# 04_Incense_MCU.net
KiCad netlist of a schematic drawn in Altium Designer
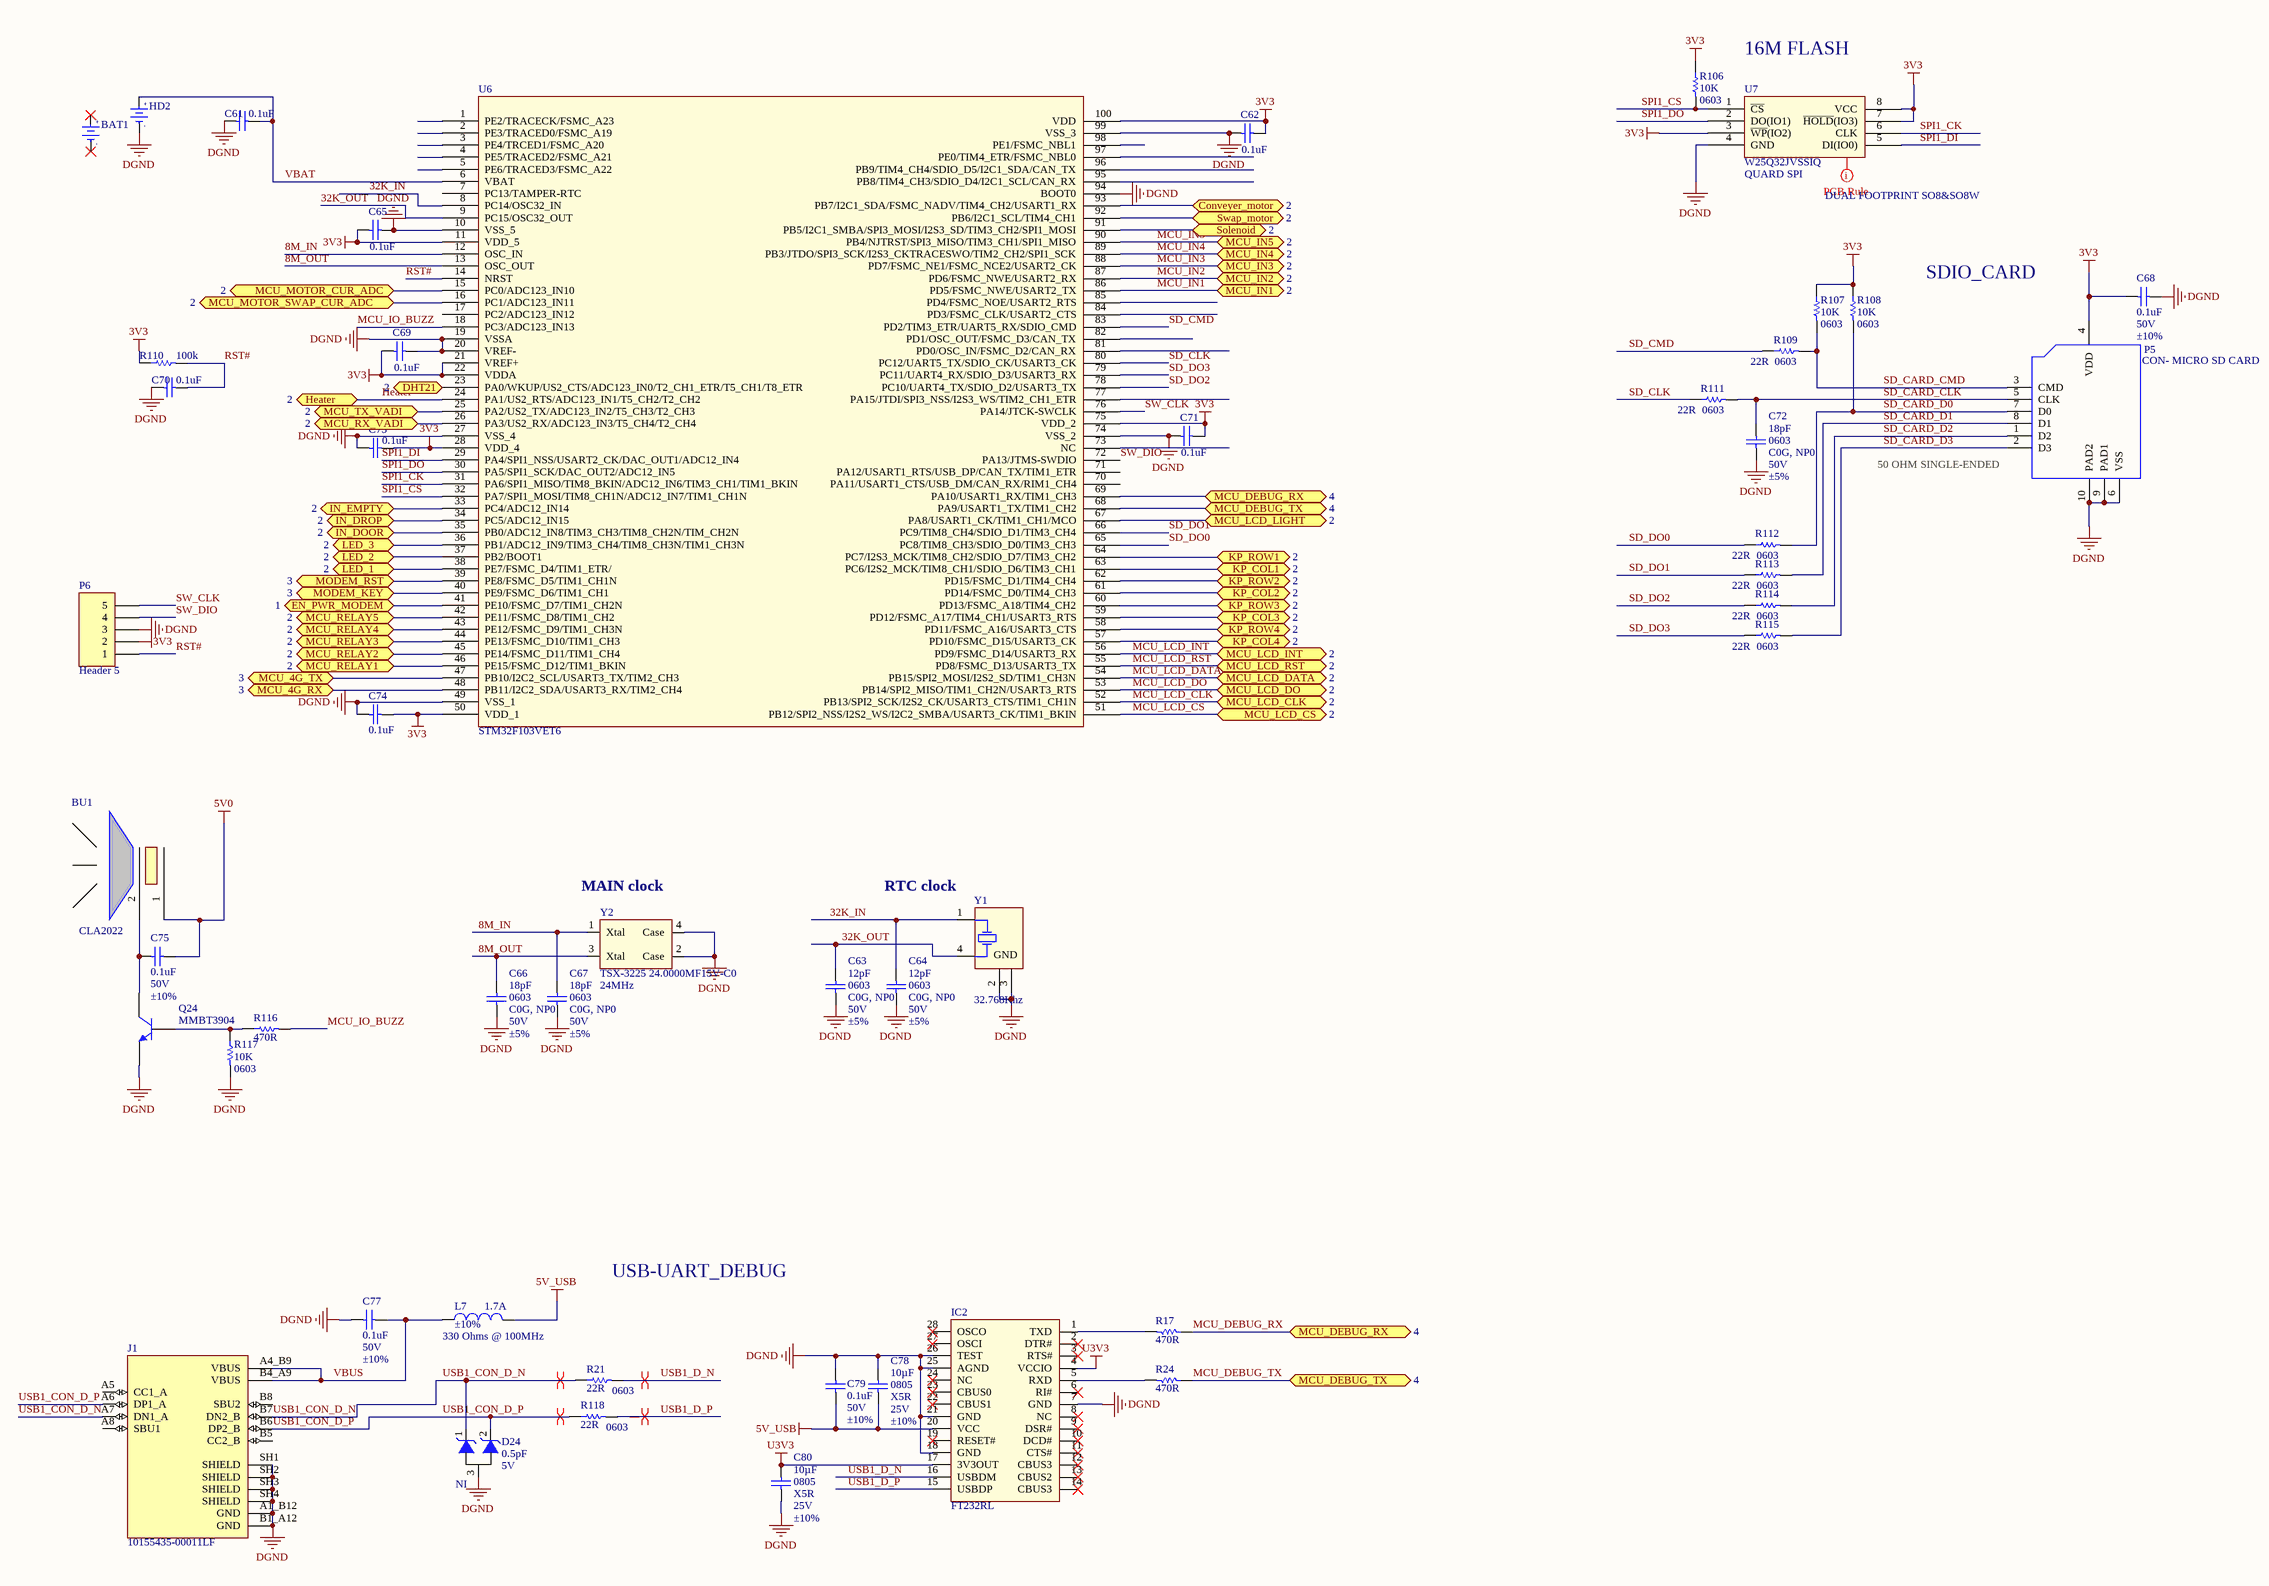
[diagram p0: 04_Incense_MCU.SchDoc]

(export (version "E")
  (design (tool "Eeschema 10.0.6"))
  (components
    (comp (ref "BAT1")
      (value "CR1220")
      (footprint "De Pin Cr1220")
      (description "CR1220 BATTERY")
      (fields (field (name "MANUFACTURER1_PART#") "PIN CR1220 Lithium"))
      (libsource (lib "Schlib1") (part "CR1220 SMD"))
    )
    (comp (ref "BU1")
      (value "CLA2022")
      (footprint "BUZZ_5V_D12X7.5MM")
      (description "BUZZ 5V 12095 12x9.5mm")
      (fields (field (name "MANUFACTURER2_PART#") "5V 9.5x12MM"))
      (libsource (lib "VSM_SES-MAIN_REV04B") (part "PKM13EPYH4000"))
    )
    (comp (ref "C61")
      (value "0.1uF,0805,16v")
      (footprint "CAP 0603")
      (description "CAP CER 0.1UF 50V X7R 0603")
      (fields
        (field (name "=VALUE") "0.1uF")
        (field (name "MANUFACTURER1_PART#") "CL10B104KB8NNNC")
        (field (name "PUBLISHER") "Altium Limited")
      )
      (libsource (lib "Miscellaneous Devices") (part "Cap"))
    )
    (comp (ref "C62")
      (value "Cap")
      (footprint "CAP 0603")
      (description "CAP CER 0.1UF 50V X7R 0603")
      (fields
        (field (name "=VALUE") "0.1uF")
        (field (name "MANUFACTURER1_PART#") "CL10B104KB8NNNC")
        (field (name "PUBLISHER") "Altium Limited")
      )
      (libsource (lib "Miscellaneous Devices") (part "Cap"))
    )
    (comp (ref "C63")
      (value "12pF")
      (footprint "0603")
      (description "CAP-CER,SMD;12PF,5%,50V,C0G/NPO 0603")
      (fields
        (field (name "MATERIAL") "C0G, NP0")
        (field (name "VOLTAGE") "50V")
        (field (name "TOLERANCE") "±5%")
        (field (name "MANUFACTURER1_PART#") "CC0603JRNPO9BN120")
      )
      (libsource (lib "Slider") (part "Cap"))
    )
    (comp (ref "C64")
      (value "12pF")
      (footprint "0603")
      (description "CAP-CER,SMD;12PF,5%,50V,C0G/NPO 0603")
      (fields
        (field (name "MATERIAL") "C0G, NP0")
        (field (name "VOLTAGE") "50V")
        (field (name "TOLERANCE") "±5%")
        (field (name "MANUFACTURER1_PART#") "CC0603JRNPO9BN120")
      )
      (libsource (lib "Slider") (part "Cap"))
    )
    (comp (ref "C65")
      (value "Cap")
      (footprint "cap 0603")
      (description "CAP CER 0.1UF 50V X7R 0603")
      (fields
        (field (name "=VALUE") "0.1uF")
        (field (name "MANUFACTURER1_PART#") "CL10B104KB8NNNC")
        (field (name "PUBLISHER") "Altium Limited")
      )
      (libsource (lib "Miscellaneous Devices") (part "Cap"))
    )
    (comp (ref "C66")
      (value "18pF")
      (footprint "0603")
      (description "CAP CER 18PF 50V C0G/NP0 0603")
      (fields
        (field (name "MATERIAL") "C0G, NP0")
        (field (name "VOLTAGE") "50V")
        (field (name "TOLERANCE") "±5%")
        (field (name "MANUFACTURER1_PART#") "CL10C180JB81PNC")
        (field (name "MANUFACTURER2_PART#") "CC0603JRNPO9BN180")
      )
      (libsource (lib "Slider") (part "Cap"))
    )
    (comp (ref "C67")
      (value "18pF")
      (footprint "0603")
      (description "CAP CER 18PF 50V C0G/NP0 0603")
      (fields
        (field (name "MATERIAL") "C0G, NP0")
        (field (name "VOLTAGE") "50V")
        (field (name "TOLERANCE") "±5%")
        (field (name "MANUFACTURER1_PART#") "CL10C180JB81PNC")
        (field (name "MANUFACTURER2_PART#") "CC0603JRNPO9BN180")
      )
      (libsource (lib "Slider") (part "Cap"))
    )
    (comp (ref "C68")
      (value "0.1uF")
      (footprint "CAP 0603")
      (description "CAP-CER,SMD;0.1UF,10%,50V,X7R,0603")
      (fields
        (field (name "VOLTAGE") "50V")
        (field (name "TOLERANCE") "±10%")
        (field (name "MANUFACTURER1_PART#") "CL10B104KB8NNNC")
        (field (name "MANUFACTURER2_PART#") "M0603X104K050TAX")
      )
      (libsource (lib "Slider") (part "Cap"))
    )
    (comp (ref "C69")
      (value "Cap")
      (footprint "CAP 0603")
      (description "CAP CER 0.1UF 50V X7R 0603")
      (fields
        (field (name "=VALUE") "0.1uF")
        (field (name "MANUFACTURER1_PART#") "CL10B104KB8NNNC")
        (field (name "PUBLISHER") "Altium Limited")
      )
      (libsource (lib "Miscellaneous Devices") (part "Cap"))
    )
    (comp (ref "C70")
      (value "Cap")
      (footprint "CAP 0603")
      (description "CAP CER 0.1UF 50V X7R 0603")
      (fields
        (field (name "=VALUE") "0.1uF")
        (field (name "MANUFACTURER1_PART#") "CL10B104KB8NNNC")
        (field (name "PUBLISHER") "Altium Limited")
      )
      (libsource (lib "Miscellaneous Devices") (part "Cap"))
    )
    (comp (ref "C71")
      (value "0.1uF")
      (footprint "CAP 0603")
      (description "CAP-CER,SMD;0.1UF,10%,50V,X7R,0603")
      (fields
        (field (name "MANUFACTURER1_PART#") "CL10B104KB8NNNC")
        (field (name "Comment") "Cap")
        (field (name "PUBLISHER") "Altium Limited")
      )
      (libsource (lib "Miscellaneous Devices") (part "Cap"))
    )
    (comp (ref "C72")
      (value "18pF")
      (footprint "0603")
      (description "CAP CER 18PF 50V C0G/NP0 0603")
      (fields
        (field (name "MATERIAL") "C0G, NP0")
        (field (name "VOLTAGE") "50V")
        (field (name "TOLERANCE") "±5%")
        (field (name "MANUFACTURER1_PART#") "CL10C180JB81PNC")
        (field (name "MANUFACTURER2_PART#") "CC0603JRNPO9BN180")
      )
      (libsource (lib "Slider") (part "Cap"))
    )
    (comp (ref "C73")
      (value "0.1uF")
      (footprint "CAP 0603")
      (description "CAP-CER,SMD;0.1UF,10%,50V,X7R,0603")
      (fields
        (field (name "MANUFACTURER1_PART#") "CL10B104KB8NNNC")
        (field (name "Comment") "Cap")
        (field (name "PUBLISHER") "Altium Limited")
      )
      (libsource (lib "Miscellaneous Devices") (part "Cap"))
    )
    (comp (ref "C74")
      (value "0.1uF")
      (footprint "CAP 0603")
      (description "CAP-CER,SMD;0.1UF,10%,50V,X7R,0603")
      (fields
        (field (name "MANUFACTURER1_PART#") "CL10B104KB8NNNC")
        (field (name "Comment") "Cap")
        (field (name "PUBLISHER") "Altium Limited")
      )
      (libsource (lib "Miscellaneous Devices") (part "Cap"))
    )
    (comp (ref "C75")
      (value "0.1uF")
      (footprint "CAP 0603")
      (description "CAP-CER,SMD;0.1UF,10%,50V,X7R,0603")
      (fields
        (field (name "VOLTAGE") "50V")
        (field (name "TOLERANCE") "±10%")
        (field (name "MANUFACTURER1_PART#") "CL10B104KB8NNNC")
        (field (name "MANUFACTURER2_PART#") "M0603X104K050TAX")
      )
      (libsource (lib "Slider") (part "Cap"))
    )
    (comp (ref "C77")
      (value "0.1uF")
      (footprint "CAP 0603")
      (description "CAP-CER,SMD;0.1UF,10%,50V,X7R,0603")
      (fields
        (field (name "VOLTAGE") "50V")
        (field (name "TOLERANCE") "±10%")
        (field (name "MANUFACTURER1_PART#") "CL10B104KB8NNNC")
        (field (name "MANUFACTURER2_PART#") "M0603X104K050TAX")
      )
      (libsource (lib "Slider") (part "Cap"))
    )
    (comp (ref "C78")
      (value "10µF")
      (footprint "CAP 0805")
      (description "CAP-CER,SMD;10UF,10%,25V,X5R,0805")
      (fields
        (field (name "MANUFACTURER1_PART#") "TMK212BBJ106KG-T")
        (field (name "MANUFACTURER2_PART#") "CL21A106KAYNNNG")
        (field (name "PACKAGE") "0805")
        (field (name "VOLTAGE") "25V")
        (field (name "TOLERANCE") "±10%")
        (field (name "MATERIAL") "X5R")
      )
      (libsource (lib "Full") (part "Cap-NP-100"))
    )
    (comp (ref "C79")
      (value "0.1uF")
      (footprint "CAP 0603")
      (description "CAP-CER,SMD;0.1UF,10%,50V,X7R,0603")
      (fields
        (field (name "VOLTAGE") "50V")
        (field (name "TOLERANCE") "±10%")
        (field (name "MANUFACTURER1_PART#") "CL10B104KB8NNNC")
        (field (name "MANUFACTURER2_PART#") "M0603X104K050TAX")
      )
      (libsource (lib "Slider") (part "Cap"))
    )
    (comp (ref "C80")
      (value "10µF")
      (footprint "CAP 0805")
      (description "CAP-CER,SMD;10UF,10%,25V,X5R,0805")
      (fields
        (field (name "MANUFACTURER1_PART#") "TMK212BBJ106KG-T")
        (field (name "MANUFACTURER2_PART#") "CL21A106KAYNNNG")
        (field (name "PACKAGE") "0805")
        (field (name "VOLTAGE") "25V")
        (field (name "TOLERANCE") "±10%")
        (field (name "MATERIAL") "X5R")
      )
      (libsource (lib "Full") (part "Cap-NP-100"))
    )
    (comp (ref "D24")
      (value "ESDR0502BT1G")
      (footprint "SOT-416")
      (description "5V, ESD PROTECTION DEVICES, SOT-23")
      (fields
        (field (name "MANUFACTURER2_PART#") "DF3D6.8MS,LF")
        (field (name "POWER") "320W")
        (field (name "CAPACITANCE") "0.5pF")
        (field (name "VOLTAGE") "5V")
        (field (name "NI_MARK") "NI")
      )
      (libsource (lib "My Library") (part "TVS_DUAL_SIGNAL_5V_SOT23"))
    )
    (comp (ref "HD2")
      (value "CR1220-2ZX")
      (footprint "BATTERY HOLDER CR1220 SMD")
      (description "CR1220 SMD HOLDER")
      (fields (field (name "MANUFACTURER2_PART#") "BH-122A-5"))
      (libsource (lib "Schlib1") (part "CR1220 SMD"))
    )
    (comp (ref "IC2")
      (value "FT232RL")
      (footprint "FT232")
      (description "IC USB FS SERIAL UART 28-SSOP")
      (fields
        (field (name "MANUFACTURER1_PART#") "FT232RL-REEL")
        (field (name "MANUFACTURER2_PART#") "PL2303HX")
      )
      (libsource (lib "PART") (part "PL2303HX"))
    )
    (comp (ref "J1")
      (value "10155435-00011LF")
      (footprint "AMPHENOL_10155435-00011LF")
      (description "USB TYPE C R/A SMT 16PIN")
      (fields (field (name "MF") "Amphenol ICC (FCI)"))
      (libsource (lib "10155435-00011LF") (part "10155435-00011LF"))
    )
    (comp (ref "L7")
      (value "330 Ohms @ 100MHz")
      (footprint "FB 0603")
      (description "FERRITE BEAD 330 OHM 0603 1LN")
      (fields
        (field (name "MANUFACTURER1_PART#") "MPZ1608S331ATA00")
        (field (name "MANUFACTURER2_PART#") "BLM18KG331SN1D")
        (field (name "CURRENT") "1.7A")
        (field (name "TOLERANCE") "±10%")
      )
      (libsource (lib "Full") (part "inductor 2.2uF"))
    )
    (comp (ref "P5")
      (value "CON- MICRO SD CARD")
      (footprint "SD-01A")
      (description "SMD Card Sockets")
      (fields (field (name "MANUFACTURER1_PART#") "SD-01A"))
      (libsource (lib "VDM_V1.0") (part "CON- MICRO SD CARD"))
    )
    (comp (ref "P6")
      (value "Header 5")
      (footprint "HDR1X5")
      (description "Header, 5-Pin,2.54mm")
      (fields (field (name "PUBLISHER") "Altium Limited"))
      (libsource (lib "Miscellaneous Connectors") (part "Header 5"))
    )
    (comp (ref "Q24")
      (value "MMBT3904")
      (footprint "SOT-23")
      (description "NPN 200mA 40V 350mW SOT-23 Transistors")
      (libsource (lib "Miscellaneous Devices") (part "NPN"))
    )
    (comp (ref "R17")
      (value "470R")
      (footprint "res 0603")
      (description "RES SMD, 470 OHM 5% 1/8W 0603")
      (fields
        (field (name "MANUFACTURER1_PART#") "RK73B1JTTD471J")
        (field (name "MANUFACTURER2_PART#") "RMCF0603JT470R")
      )
      (libsource (lib "Full") (part "Res0.3"))
    )
    (comp (ref "R21")
      (value "22R")
      (footprint "res 0603")
      (description "RES 22 OHM 5% 1/10W 0603")
      (fields
        (field (name "MANUFACTURER1_PART#") "RC0603JR-0722RL")
        (field (name "MANUFACTURER2_PART#") "RMCF0603JT22R0")
        (field (name "PCB FOOTPRINT") "0603")
      )
      (libsource (lib "Full") (part "Res0.3"))
    )
    (comp (ref "R24")
      (value "470R")
      (footprint "res 0603")
      (description "RES SMD, 470 OHM 5% 1/8W 0603")
      (fields
        (field (name "MANUFACTURER1_PART#") "RK73B1JTTD471J")
        (field (name "MANUFACTURER2_PART#") "RMCF0603JT470R")
      )
      (libsource (lib "Full") (part "Res0.3"))
    )
    (comp (ref "R106")
      (value "10K")
      (footprint "res 0603")
      (description "RES SMD,10K OHM 5% 1/10W 0603")
      (fields
        (field (name "MANUFACTURER1_PART#") "RMCF0603JT10K0")
        (field (name "MANUFACTURER2_PART#") "R0603J10KKDX")
        (field (name "PCB FOOTPRINT") "0603")
      )
      (libsource (lib "altium-import") (part "root_3_Res0.3_"))
    )
    (comp (ref "R107")
      (value "10K")
      (footprint "res 0603")
      (description "RES SMD,10K OHM 5% 1/10W 0603")
      (fields
        (field (name "MANUFACTURER1_PART#") "RMCF0603JT10K0")
        (field (name "MANUFACTURER2_PART#") "R0603J10KKDX")
        (field (name "PCB FOOTPRINT") "0603")
      )
      (libsource (lib "altium-import") (part "root_3_Res0.3_"))
    )
    (comp (ref "R108")
      (value "10K")
      (footprint "res 0603")
      (description "RES SMD,10K OHM 5% 1/10W 0603")
      (fields
        (field (name "MANUFACTURER1_PART#") "RMCF0603JT10K0")
        (field (name "MANUFACTURER2_PART#") "R0603J10KKDX")
        (field (name "PCB FOOTPRINT") "0603")
      )
      (libsource (lib "altium-import") (part "root_3_Res0.3_"))
    )
    (comp (ref "R109")
      (value "22R")
      (footprint "res 0603")
      (description "RES 22 OHM 5% 1/10W 0603")
      (fields
        (field (name "MANUFACTURER1_PART#") "RC0603JR-0722RL")
        (field (name "MANUFACTURER2_PART#") "RMCF0603JT22R0")
        (field (name "PCB FOOTPRINT") "0603")
      )
      (libsource (lib "Full") (part "Res0.3"))
    )
    (comp (ref "R110")
      (value "100k")
      (footprint "RES 0603")
      (description "RES 100K OHM 1% 1/10W 0603")
      (fields
        (field (name "MANUFACTURER1_PART#") "RMCF0603FT100K")
        (field (name "Comment") "100k, 0603")
        (field (name "PUBLISHER") "Altium Limited")
      )
      (libsource (lib "Miscellaneous Devices") (part "Res1"))
    )
    (comp (ref "R111")
      (value "22R")
      (footprint "res 0603")
      (description "RES 22 OHM 5% 1/10W 0603")
      (fields
        (field (name "MANUFACTURER1_PART#") "RC0603JR-0722RL")
        (field (name "MANUFACTURER2_PART#") "RMCF0603JT22R0")
        (field (name "PCB FOOTPRINT") "0603")
      )
      (libsource (lib "Full") (part "Res0.3"))
    )
    (comp (ref "R112")
      (value "22R")
      (footprint "res 0603")
      (description "RES 22 OHM 5% 1/10W 0603")
      (fields
        (field (name "MANUFACTURER1_PART#") "RC0603JR-0722RL")
        (field (name "MANUFACTURER2_PART#") "RMCF0603JT22R0")
        (field (name "PCB FOOTPRINT") "0603")
      )
      (libsource (lib "Full") (part "Res0.3"))
    )
    (comp (ref "R113")
      (value "22R")
      (footprint "res 0603")
      (description "RES 22 OHM 5% 1/10W 0603")
      (fields
        (field (name "MANUFACTURER1_PART#") "RC0603JR-0722RL")
        (field (name "MANUFACTURER2_PART#") "RMCF0603JT22R0")
        (field (name "PCB FOOTPRINT") "0603")
      )
      (libsource (lib "Full") (part "Res0.3"))
    )
    (comp (ref "R114")
      (value "22R")
      (footprint "res 0603")
      (description "RES 22 OHM 5% 1/10W 0603")
      (fields
        (field (name "MANUFACTURER1_PART#") "RC0603JR-0722RL")
        (field (name "MANUFACTURER2_PART#") "RMCF0603JT22R0")
        (field (name "PCB FOOTPRINT") "0603")
      )
      (libsource (lib "Full") (part "Res0.3"))
    )
    (comp (ref "R115")
      (value "22R")
      (footprint "res 0603")
      (description "RES 22 OHM 5% 1/10W 0603")
      (fields
        (field (name "MANUFACTURER1_PART#") "RC0603JR-0722RL")
        (field (name "MANUFACTURER2_PART#") "RMCF0603JT22R0")
        (field (name "PCB FOOTPRINT") "0603")
      )
      (libsource (lib "Full") (part "Res0.3"))
    )
    (comp (ref "R116")
      (value "470R")
      (footprint "res 0603")
      (description "RES SMD, 470 OHM 5% 1/8W 0603")
      (fields
        (field (name "MANUFACTURER1_PART#") "RK73B1JTTD471J")
        (field (name "MANUFACTURER2_PART#") "RMCF0603JT470R")
      )
      (libsource (lib "Full") (part "Res0.3"))
    )
    (comp (ref "R117")
      (value "10K")
      (footprint "res 0603")
      (description "RES SMD,10K OHM 5% 1/10W 0603")
      (fields
        (field (name "MANUFACTURER1_PART#") "RMCF0603JT10K0")
        (field (name "MANUFACTURER2_PART#") "R0603J10KKDX")
        (field (name "PCB FOOTPRINT") "0603")
      )
      (libsource (lib "altium-import") (part "root_3_Res0.3_"))
    )
    (comp (ref "R118")
      (value "22R")
      (footprint "res 0603")
      (description "RES 22 OHM 5% 1/10W 0603")
      (fields
        (field (name "MANUFACTURER1_PART#") "RC0603JR-0722RL")
        (field (name "MANUFACTURER2_PART#") "RMCF0603JT22R0")
        (field (name "PCB FOOTPRINT") "0603")
      )
      (libsource (lib "Full") (part "Res0.3"))
    )
    (comp (ref "U6")
      (value "STM32F103VET6")
      (footprint "LQFP100_N")
      (description "IC MCU 32BIT 512KB FLASH 100LQFP")
      (libsource (lib "hiendv_sch") (part "STM32F103VET6"))
    )
    (comp (ref "U7")
      (value "W25Q32JVSSIQ")
      (footprint "SOIC-8 208MIL")
      (description "IC FLASH 32MBIT SPI/QUAD 8SOIC")
      (fields (field (name "VOLTAGE") "2.7V ~ 3.6V") (field (name "INTERFACE") "QUARD SPI"))
      (libsource (lib "My Library") (part "IC Flash W25Q16JVSNIQ QUAD SO8"))
    )
    (comp (ref "Y1")
      (value "32.768Khz")
      (footprint "MC-306")
      (description "CRYSTAL 32.7680KHZ 12.5PF SMD")
      (fields (field (name "MANUFACTURER1_PART#") "TKD M8-32.768KHZ-12.5PF-20PPM"))
      (libsource (lib "lib") (part "XT4_32.768KHZ"))
    )
    (comp (ref "Y2")
      (value "24MHz")
      (footprint "Crystal 4SMD 32x25MM")
      (description "CRYSTAL 24.0000MHZ 18PF SMD")
      (fields
        (field (name "TOLERANCE") "±20ppm")
        (field (name "MANUFACTURER1_PART#") "TSX-3225 24.0000MF15V-C0")
      )
      (libsource (lib "Full") (part "Crystal FL0800008Q"))
    )
  )
  (nets
    (net (code "1") (name "/8M_IN") (class "Default")
      (node (ref "C67") (pin "1") (pinfunction "1_1") (pintype "passive"))
      (node (ref "U6") (pin "12") (pinfunction "OSC_IN_12") (pintype "passive"))
      (node (ref "Y2") (pin "1") (pinfunction "Xtal_1") (pintype "passive"))
    )
    (net (code "2") (name "/8M_OUT") (class "Default")
      (node (ref "C66") (pin "1") (pinfunction "1_1") (pintype "passive"))
      (node (ref "U6") (pin "13") (pinfunction "OSC_OUT_13") (pintype "passive"))
      (node (ref "Y2") (pin "3") (pinfunction "Xtal_3") (pintype "passive"))
    )
    (net (code "3") (name "/32K_IN") (class "Default")
      (node (ref "C64") (pin "1") (pinfunction "1_1") (pintype "passive"))
      (node (ref "U6") (pin "8") (pinfunction "PC14/OSC32_IN_8") (pintype "passive"))
      (node (ref "Y1") (pin "1") (pinfunction "XTAL_1") (pintype "passive"))
    )
    (net (code "4") (name "/32K_OUT") (class "Default")
      (node (ref "C63") (pin "1") (pinfunction "1_1") (pintype "passive"))
      (node (ref "U6") (pin "9") (pinfunction "PC15/OSC32_OUT_9") (pintype "passive"))
      (node (ref "Y1") (pin "4") (pinfunction "XTAL_4") (pintype "passive"))
    )
    (net (code "5") (name "/Conveyer_motor") (class "Default")
      (node (ref "U6") (pin "93") (pinfunction "PB7/I2C1_SDA/FSMC_NADV/TIM4_CH2/USART1_RX_93") (pintype "passive"))
    )
    (net (code "6") (name "/DHT21") (class "Default")
      (node (ref "U6") (pin "23") (pinfunction "PA0/WKUP/US2_CTS/ADC123_IN0/T2_CH1_ETR/T5_CH1/T8_ETR_23") (pintype "passive"))
    )
    (net (code "7") (name "/EN_PWR_MODEM") (class "Default")
      (node (ref "U6") (pin "41") (pinfunction "PE10/FSMC_D7/TIM1_CH2N_41") (pintype "passive"))
    )
    (net (code "8") (name "/Heater") (class "Default")
      (node (ref "U6") (pin "24") (pinfunction "PA1/US2_RTS/ADC123_IN1/T5_CH2/T2_CH2_24") (pintype "passive"))
    )
    (net (code "9") (name "/IN_DOOR") (class "Default")
      (node (ref "U6") (pin "35") (pinfunction "PB0/ADC12_IN8/TIM3_CH3/TIM8_CH2N/TIM_CH2N_35") (pintype "passive"))
    )
    (net (code "10") (name "/IN_DROP") (class "Default")
      (node (ref "U6") (pin "34") (pinfunction "PC5/ADC12_IN15_34") (pintype "passive"))
    )
    (net (code "11") (name "/IN_EMPTY") (class "Default")
      (node (ref "U6") (pin "33") (pinfunction "PC4/ADC12_IN14_33") (pintype "passive"))
    )
    (net (code "12") (name "/KP_COL1") (class "Default")
      (node (ref "U6") (pin "63") (pinfunction "PC6/I2S2_MCK/TIM8_CH1/SDIO_D6/TIM3_CH1_63") (pintype "passive"))
    )
    (net (code "13") (name "/KP_COL2") (class "Default")
      (node (ref "U6") (pin "61") (pinfunction "PD14/FSMC_D0/TIM4_CH3_61") (pintype "passive"))
    )
    (net (code "14") (name "/KP_COL3") (class "Default")
      (node (ref "U6") (pin "59") (pinfunction "PD12/FSMC_A17/TIM4_CH1/USART3_RTS_59") (pintype "passive"))
    )
    (net (code "15") (name "/KP_COL4") (class "Default")
      (node (ref "U6") (pin "57") (pinfunction "PD10/FSMC_D15/USART3_CK_57") (pintype "passive"))
    )
    (net (code "16") (name "/KP_ROW1") (class "Default")
      (node (ref "U6") (pin "64") (pinfunction "PC7/I2S3_MCK/TIM8_CH2/SDIO_D7/TIM3_CH2_64") (pintype "passive"))
    )
    (net (code "17") (name "/KP_ROW2") (class "Default")
      (node (ref "U6") (pin "62") (pinfunction "PD15/FSMC_D1/TIM4_CH4_62") (pintype "passive"))
    )
    (net (code "18") (name "/KP_ROW3") (class "Default")
      (node (ref "U6") (pin "60") (pinfunction "PD13/FSMC_A18/TIM4_CH2_60") (pintype "passive"))
    )
    (net (code "19") (name "/KP_ROW4") (class "Default")
      (node (ref "U6") (pin "58") (pinfunction "PD11/FSMC_A16/USART3_CTS_58") (pintype "passive"))
    )
    (net (code "20") (name "/LED_1") (class "Default")
      (node (ref "U6") (pin "38") (pinfunction "PE7/FSMC_D4/TIM1_ETR/_38") (pintype "passive"))
    )
    (net (code "21") (name "/LED_2") (class "Default")
      (node (ref "U6") (pin "37") (pinfunction "PB2/BOOT1_37") (pintype "passive"))
    )
    (net (code "22") (name "/LED_3") (class "Default")
      (node (ref "U6") (pin "36") (pinfunction "PB1/ADC12_IN9/TIM3_CH4/TIM8_CH3N/TIM1_CH3N_36") (pintype "passive"))
    )
    (net (code "23") (name "/MCU_4G_RX") (class "Default")
      (node (ref "U6") (pin "48") (pinfunction "PB11/I2C2_SDA/USART3_RX/TIM2_CH4_48") (pintype "passive"))
    )
    (net (code "24") (name "/MCU_4G_TX") (class "Default")
      (node (ref "U6") (pin "47") (pinfunction "PB10/I2C2_SCL/USART3_TX/TIM2_CH3_47") (pintype "passive"))
    )
    (net (code "25") (name "/MCU_DEBUG_RX") (class "Default")
      (node (ref "R17") (pin "1") (pinfunction "1_1") (pintype "passive"))
      (node (ref "U6") (pin "69") (pinfunction "PA10/USART1_RX/TIM1_CH3_69") (pintype "passive"))
    )
    (net (code "26") (name "/MCU_DEBUG_TX") (class "Default")
      (node (ref "R24") (pin "1") (pinfunction "1_1") (pintype "passive"))
      (node (ref "U6") (pin "68") (pinfunction "PA9/USART1_TX/TIM1_CH2_68") (pintype "passive"))
    )
    (net (code "27") (name "/MCU_IN1") (class "Default")
      (node (ref "U6") (pin "86") (pinfunction "PD5/FSMC_NWE/USART2_TX_86") (pintype "passive"))
    )
    (net (code "28") (name "/MCU_IN2") (class "Default")
      (node (ref "U6") (pin "87") (pinfunction "PD6/FSMC_NWE/USART2_RX_87") (pintype "passive"))
    )
    (net (code "29") (name "/MCU_IN3") (class "Default")
      (node (ref "U6") (pin "88") (pinfunction "PD7/FSMC_NE1/FSMC_NCE2/USART2_CK_88") (pintype "passive"))
    )
    (net (code "30") (name "/MCU_IN4") (class "Default")
      (node (ref "U6") (pin "89") (pinfunction "PB3/JTDO/SPI3_SCK/I2S3_CKTRACESWO/TIM2_CH2/SPI1_SCK_89") (pintype "passive"))
    )
    (net (code "31") (name "/MCU_IN5") (class "Default")
      (node (ref "U6") (pin "90") (pinfunction "PB4/NJTRST/SPI3_MISO/TIM3_CH1/SPI1_MISO_90") (pintype "passive"))
    )
    (net (code "32") (name "/MCU_IO_BUZZ") (class "Default")
      (node (ref "R116") (pin "2") (pinfunction "2_2") (pintype "passive"))
      (node (ref "U6") (pin "18") (pinfunction "PC3/ADC123_IN13_18") (pintype "passive"))
    )
    (net (code "33") (name "/MCU_LCD_CLK") (class "Default")
      (node (ref "U6") (pin "52") (pinfunction "PB13/SPI2_SCK/I2S2_CK/USART3_CTS/TIM1_CH1N_52") (pintype "passive"))
    )
    (net (code "34") (name "/MCU_LCD_CS") (class "Default")
      (node (ref "U6") (pin "51") (pinfunction "PB12/SPI2_NSS/I2S2_WS/I2C2_SMBA/USART3_CK/TIM1_BKIN_51") (pintype "passive"))
    )
    (net (code "35") (name "/MCU_LCD_DATA") (class "Default")
      (node (ref "U6") (pin "54") (pinfunction "PB15/SPI2_MOSI/I2S2_SD/TIM1_CH3N_54") (pintype "passive"))
    )
    (net (code "36") (name "/MCU_LCD_DO") (class "Default")
      (node (ref "U6") (pin "53") (pinfunction "PB14/SPI2_MISO/TIM1_CH2N/USART3_RTS_53") (pintype "passive"))
    )
    (net (code "37") (name "/MCU_LCD_INT") (class "Default")
      (node (ref "U6") (pin "56") (pinfunction "PD9/FSMC_D14/USART3_RX_56") (pintype "passive"))
    )
    (net (code "38") (name "/MCU_LCD_LIGHT") (class "Default")
      (node (ref "U6") (pin "67") (pinfunction "PA8/USART1_CK/TIM1_CH1/MCO_67") (pintype "passive"))
    )
    (net (code "39") (name "/MCU_LCD_RST") (class "Default")
      (node (ref "U6") (pin "55") (pinfunction "PD8/FSMC_D13/USART3_TX_55") (pintype "passive"))
    )
    (net (code "40") (name "/MCU_MOTOR_CUR_ADC") (class "Default")
      (node (ref "U6") (pin "15") (pinfunction "PC0/ADC123_IN10_15") (pintype "passive"))
    )
    (net (code "41") (name "/MCU_MOTOR_SWAP_CUR_ADC") (class "Default")
      (node (ref "U6") (pin "16") (pinfunction "PC1/ADC123_IN11_16") (pintype "passive"))
    )
    (net (code "42") (name "/MCU_RELAY1") (class "Default")
      (node (ref "U6") (pin "46") (pinfunction "PE15/FSMC_D12/TIM1_BKIN_46") (pintype "passive"))
    )
    (net (code "43") (name "/MCU_RELAY2") (class "Default")
      (node (ref "U6") (pin "45") (pinfunction "PE14/FSMC_D11/TIM1_CH4_45") (pintype "passive"))
    )
    (net (code "44") (name "/MCU_RELAY3") (class "Default")
      (node (ref "U6") (pin "44") (pinfunction "PE13/FSMC_D10/TIM1_CH3_44") (pintype "passive"))
    )
    (net (code "45") (name "/MCU_RELAY4") (class "Default")
      (node (ref "U6") (pin "43") (pinfunction "PE12/FSMC_D9/TIM1_CH3N_43") (pintype "passive"))
    )
    (net (code "46") (name "/MCU_RELAY5") (class "Default")
      (node (ref "U6") (pin "42") (pinfunction "PE11/FSMC_D8/TIM1_CH2_42") (pintype "passive"))
    )
    (net (code "47") (name "/MCU_RX_VADI") (class "Default")
      (node (ref "U6") (pin "26") (pinfunction "PA3/US2_RX/ADC123_IN3/T5_CH4/T2_CH4_26") (pintype "passive"))
    )
    (net (code "48") (name "/MCU_TX_VADI") (class "Default")
      (node (ref "U6") (pin "25") (pinfunction "PA2/US2_TX/ADC123_IN2/T5_CH3/T2_CH3_25") (pintype "passive"))
    )
    (net (code "49") (name "/MODEM_KEY") (class "Default")
      (node (ref "U6") (pin "40") (pinfunction "PE9/FSMC_D6/TIM1_CH1_40") (pintype "passive"))
    )
    (net (code "50") (name "/MODEM_RST") (class "Default")
      (node (ref "U6") (pin "39") (pinfunction "PE8/FSMC_D5/TIM1_CH1N_39") (pintype "passive"))
    )
    (net (code "51") (name "/RST#") (class "Default")
      (node (ref "C70") (pin "2") (pinfunction "2_2") (pintype "passive"))
      (node (ref "P6") (pin "1") (pinfunction "1_1") (pintype "passive"))
      (node (ref "R110") (pin "2") (pinfunction "2_2") (pintype "passive"))
      (node (ref "U6") (pin "14") (pinfunction "NRST_14") (pintype "passive"))
    )
    (net (code "52") (name "/SD_CARD_CLK") (class "Default")
      (node (ref "C72") (pin "1") (pinfunction "1_1") (pintype "passive"))
      (node (ref "P5") (pin "5") (pinfunction "CLK_5") (pintype "passive"))
      (node (ref "R111") (pin "2") (pinfunction "2_2") (pintype "passive"))
    )
    (net (code "53") (name "/SD_CARD_CMD") (class "Default")
      (node (ref "P5") (pin "3") (pinfunction "CMD_3") (pintype "passive"))
      (node (ref "R107") (pin "2") (pinfunction "2_2") (pintype "passive"))
      (node (ref "R109") (pin "2") (pinfunction "2_2") (pintype "passive"))
    )
    (net (code "54") (name "/SD_CARD_D0") (class "Default")
      (node (ref "P5") (pin "7") (pinfunction "D0_7") (pintype "passive"))
      (node (ref "R108") (pin "2") (pinfunction "2_2") (pintype "passive"))
      (node (ref "R112") (pin "2") (pinfunction "2_2") (pintype "passive"))
    )
    (net (code "55") (name "/SD_CARD_D1") (class "Default")
      (node (ref "P5") (pin "8") (pinfunction "D1_8") (pintype "passive"))
      (node (ref "R113") (pin "2") (pinfunction "2_2") (pintype "passive"))
    )
    (net (code "56") (name "/SD_CARD_D2") (class "Default")
      (node (ref "P5") (pin "1") (pinfunction "D2_1") (pintype "passive"))
      (node (ref "R114") (pin "2") (pinfunction "2_2") (pintype "passive"))
    )
    (net (code "57") (name "/SD_CARD_D3") (class "Default")
      (node (ref "P5") (pin "2") (pinfunction "D3_2") (pintype "passive"))
      (node (ref "R115") (pin "2") (pinfunction "2_2") (pintype "passive"))
    )
    (net (code "58") (name "/SD_CLK") (class "Default")
      (node (ref "R111") (pin "1") (pinfunction "1_1") (pintype "passive"))
      (node (ref "U6") (pin "80") (pinfunction "PC12/UART5_TX/SDIO_CK/USART3_CK_80") (pintype "passive"))
    )
    (net (code "59") (name "/SD_CMD") (class "Default")
      (node (ref "R109") (pin "1") (pinfunction "1_1") (pintype "passive"))
      (node (ref "U6") (pin "83") (pinfunction "PD2/TIM3_ETR/UART5_RX/SDIO_CMD_83") (pintype "passive"))
    )
    (net (code "60") (name "/SD_DO0") (class "Default")
      (node (ref "R112") (pin "1") (pinfunction "1_1") (pintype "passive"))
      (node (ref "U6") (pin "65") (pinfunction "PC8/TIM8_CH3/SDIO_D0/TIM3_CH3_65") (pintype "passive"))
    )
    (net (code "61") (name "/SD_DO1") (class "Default")
      (node (ref "R113") (pin "1") (pinfunction "1_1") (pintype "passive"))
      (node (ref "U6") (pin "66") (pinfunction "PC9/TIM8_CH4/SDIO_D1/TIM3_CH4_66") (pintype "passive"))
    )
    (net (code "62") (name "/SD_DO2") (class "Default")
      (node (ref "R114") (pin "1") (pinfunction "1_1") (pintype "passive"))
      (node (ref "U6") (pin "78") (pinfunction "PC10/UART4_TX/SDIO_D2/USART3_TX_78") (pintype "passive"))
    )
    (net (code "63") (name "/SD_DO3") (class "Default")
      (node (ref "R115") (pin "1") (pinfunction "1_1") (pintype "passive"))
      (node (ref "U6") (pin "79") (pinfunction "PC11/UART4_RX/SDIO_D3/USART3_RX_79") (pintype "passive"))
    )
    (net (code "64") (name "/SPI1_CK") (class "Default")
      (node (ref "U6") (pin "31") (pinfunction "PA6/SPI1_MISO/TIM8_BKIN/ADC12_IN6/TIM3_CH1/TIM1_BKIN_31") (pintype "passive"))
      (node (ref "U7") (pin "6") (pinfunction "CLK_6") (pintype "passive"))
    )
    (net (code "65") (name "/SPI1_CS") (class "Default")
      (node (ref "R106") (pin "2") (pinfunction "2_2") (pintype "passive"))
      (node (ref "U6") (pin "32") (pinfunction "PA7/SPI1_MOSI/TIM8_CH1N/ADC12_IN7/TIM1_CH1N_32") (pintype "passive"))
      (node (ref "U7") (pin "1") (pinfunction "~{CS}_1") (pintype "passive"))
    )
    (net (code "66") (name "/SPI1_DI") (class "Default")
      (node (ref "U6") (pin "29") (pinfunction "PA4/SPI1_NSS/USART2_CK/DAC_OUT1/ADC12_IN4_29") (pintype "passive"))
      (node (ref "U7") (pin "5") (pinfunction "DI(IO0)_5") (pintype "passive"))
    )
    (net (code "67") (name "/SPI1_DO") (class "Default")
      (node (ref "U6") (pin "30") (pinfunction "PA5/SPI1_SCK/DAC_OUT2/ADC12_IN5_30") (pintype "passive"))
      (node (ref "U7") (pin "2") (pinfunction "DO(IO1)_2") (pintype "passive"))
    )
    (net (code "68") (name "/SW_CLK") (class "Default")
      (node (ref "P6") (pin "5") (pinfunction "5_5") (pintype "passive"))
      (node (ref "U6") (pin "76") (pinfunction "PA14/JTCK-SWCLK_76") (pintype "passive"))
    )
    (net (code "69") (name "/SW_DIO") (class "Default")
      (node (ref "P6") (pin "4") (pinfunction "4_4") (pintype "passive"))
      (node (ref "U6") (pin "72") (pinfunction "PA13/JTMS-SWDIO_72") (pintype "passive"))
    )
    (net (code "70") (name "/Solenoid") (class "Default")
      (node (ref "U6") (pin "91") (pinfunction "PB5/I2C1_SMBA/SPI3_MOSI/I2S3_SD/TIM3_CH2/SPI1_MOSI_91") (pintype "passive"))
    )
    (net (code "71") (name "/Swap_motor") (class "Default")
      (node (ref "U6") (pin "92") (pinfunction "PB6/I2C1_SCL/TIM4_CH1_92") (pintype "passive"))
    )
    (net (code "72") (name "/USB1_CON_D_N") (class "Default")
      (node (ref "D24") (pin "1") (pinfunction "K_1") (pintype "passive"))
      (node (ref "J1") (pin "A7") (pinfunction "DN1_A_A7") (pintype "bidirectional"))
      (node (ref "J1") (pin "B7") (pinfunction "DN2_B_B7") (pintype "bidirectional"))
      (node (ref "R21") (pin "1") (pinfunction "1_1") (pintype "passive"))
    )
    (net (code "73") (name "/USB1_CON_D_P") (class "Default")
      (node (ref "D24") (pin "2") (pinfunction "K_2") (pintype "passive"))
      (node (ref "J1") (pin "A6") (pinfunction "DP1_A_A6") (pintype "bidirectional"))
      (node (ref "J1") (pin "B6") (pinfunction "DP2_B_B6") (pintype "bidirectional"))
      (node (ref "R118") (pin "1") (pinfunction "1_1") (pintype "passive"))
    )
    (net (code "74") (name "/USB1_D_N") (class "Default")
      (node (ref "IC2") (pin "16") (pinfunction "USBDM_16") (pintype "passive"))
      (node (ref "R21") (pin "2") (pinfunction "2_2") (pintype "passive"))
    )
    (net (code "75") (name "/USB1_D_P") (class "Default")
      (node (ref "IC2") (pin "15") (pinfunction "USBDP_15") (pintype "passive"))
      (node (ref "R118") (pin "2") (pinfunction "2_2") (pintype "passive"))
    )
    (net (code "76") (name "/VBAT") (class "Default")
      (node (ref "C61") (pin "2") (pinfunction "2_2") (pintype "passive"))
      (node (ref "HD2") (pin "1") (pinfunction "+3V_1") (pintype "passive"))
      (node (ref "U6") (pin "6") (pinfunction "VBAT_6") (pintype "passive"))
    )
    (net (code "77") (name "/VBUS") (class "Default")
      (node (ref "C77") (pin "2") (pinfunction "2_2") (pintype "passive"))
      (node (ref "J1") (pin "A4_B9") (pinfunction "VBUS_A4_B9") (pintype "power_in"))
      (node (ref "J1") (pin "B4_A9") (pinfunction "VBUS_B4_A9") (pintype "power_in"))
      (node (ref "L7") (pin "1") (pinfunction "1_1") (pintype "passive"))
    )
    (net (code "78") (name "3V3") (class "Default")
      (node (ref "C62") (pin "2") (pinfunction "2_2") (pintype "passive"))
      (node (ref "C65") (pin "1") (pinfunction "1_1") (pintype "passive"))
      (node (ref "C68") (pin "1") (pinfunction "1_1") (pintype "passive"))
      (node (ref "C69") (pin "1") (pinfunction "1_1") (pintype "passive"))
      (node (ref "C71") (pin "2") (pinfunction "2_2") (pintype "passive"))
      (node (ref "C73") (pin "1") (pinfunction "1_1") (pintype "passive"))
      (node (ref "C74") (pin "1") (pinfunction "1_1") (pintype "passive"))
      (node (ref "P5") (pin "4") (pinfunction "VDD_4") (pintype "passive"))
      (node (ref "P6") (pin "2") (pinfunction "2_2") (pintype "passive"))
      (node (ref "R106") (pin "1") (pinfunction "1_1") (pintype "passive"))
      (node (ref "R107") (pin "1") (pinfunction "1_1") (pintype "passive"))
      (node (ref "R108") (pin "1") (pinfunction "1_1") (pintype "passive"))
      (node (ref "R110") (pin "1") (pinfunction "1_1") (pintype "passive"))
      (node (ref "U6") (pin "100") (pinfunction "VDD_100") (pintype "passive"))
      (node (ref "U6") (pin "11") (pinfunction "VDD_5_11") (pintype "passive"))
      (node (ref "U6") (pin "21") (pinfunction "VREF+_21") (pintype "passive"))
      (node (ref "U6") (pin "22") (pinfunction "VDDA_22") (pintype "passive"))
      (node (ref "U6") (pin "28") (pinfunction "VDD_4_28") (pintype "passive"))
      (node (ref "U6") (pin "50") (pinfunction "VDD_1_50") (pintype "passive"))
      (node (ref "U6") (pin "75") (pinfunction "VDD_2_75") (pintype "passive"))
      (node (ref "U7") (pin "3") (pinfunction "~{WP}(IO2)_3") (pintype "passive"))
      (node (ref "U7") (pin "7") (pinfunction "~{HOLD}(IO3)_7") (pintype "passive"))
      (node (ref "U7") (pin "8") (pinfunction "VCC_8") (pintype "passive"))
    )
    (net (code "79") (name "5V0") (class "Default")
      (node (ref "BU1") (pin "1") (pinfunction "PIN1_1") (pintype "passive"))
      (node (ref "C75") (pin "2") (pinfunction "2_2") (pintype "passive"))
    )
    (net (code "80") (name "5V_USB") (class "Default")
      (node (ref "C78") (pin "2") (pinfunction "2_2") (pintype "passive"))
      (node (ref "C79") (pin "1") (pinfunction "1_1") (pintype "passive"))
      (node (ref "IC2") (pin "20") (pinfunction "VCC_20") (pintype "passive"))
      (node (ref "L7") (pin "2") (pinfunction "2_2") (pintype "passive"))
    )
    (net (code "81") (name "DGND") (class "Default")
      (node (ref "C61") (pin "1") (pinfunction "1_1") (pintype "passive"))
      (node (ref "C62") (pin "1") (pinfunction "1_1") (pintype "passive"))
      (node (ref "C63") (pin "2") (pinfunction "2_2") (pintype "passive"))
      (node (ref "C64") (pin "2") (pinfunction "2_2") (pintype "passive"))
      (node (ref "C65") (pin "2") (pinfunction "2_2") (pintype "passive"))
      (node (ref "C66") (pin "2") (pinfunction "2_2") (pintype "passive"))
      (node (ref "C67") (pin "2") (pinfunction "2_2") (pintype "passive"))
      (node (ref "C68") (pin "2") (pinfunction "2_2") (pintype "passive"))
      (node (ref "C69") (pin "2") (pinfunction "2_2") (pintype "passive"))
      (node (ref "C70") (pin "1") (pinfunction "1_1") (pintype "passive"))
      (node (ref "C71") (pin "1") (pinfunction "1_1") (pintype "passive"))
      (node (ref "C72") (pin "2") (pinfunction "2_2") (pintype "passive"))
      (node (ref "C73") (pin "2") (pinfunction "2_2") (pintype "passive"))
      (node (ref "C74") (pin "2") (pinfunction "2_2") (pintype "passive"))
      (node (ref "C77") (pin "1") (pinfunction "1_1") (pintype "passive"))
      (node (ref "C78") (pin "1") (pinfunction "1_1") (pintype "passive"))
      (node (ref "C79") (pin "2") (pinfunction "2_2") (pintype "passive"))
      (node (ref "C80") (pin "2") (pinfunction "2_2") (pintype "passive"))
      (node (ref "D24") (pin "3") (pinfunction "A_3") (pintype "passive"))
      (node (ref "HD2") (pin "2") (pinfunction "GND_2") (pintype "passive"))
      (node (ref "IC2") (pin "18") (pinfunction "GND_18") (pintype "passive"))
      (node (ref "IC2") (pin "21") (pinfunction "GND_21") (pintype "passive"))
      (node (ref "IC2") (pin "25") (pinfunction "AGND_25") (pintype "passive"))
      (node (ref "IC2") (pin "26") (pinfunction "TEST_26") (pintype "passive"))
      (node (ref "IC2") (pin "7") (pinfunction "GND_7") (pintype "passive"))
      (node (ref "J1") (pin "A1_B12") (pinfunction "GND_A1_B12") (pintype "power_in"))
      (node (ref "J1") (pin "B1_A12") (pinfunction "GND_B1_A12") (pintype "power_in"))
      (node (ref "J1") (pin "SH1") (pinfunction "SHIELD_SH1") (pintype "passive"))
      (node (ref "J1") (pin "SH2") (pinfunction "SHIELD_SH2") (pintype "passive"))
      (node (ref "J1") (pin "SH3") (pinfunction "SHIELD_SH3") (pintype "passive"))
      (node (ref "J1") (pin "SH4") (pinfunction "SHIELD_SH4") (pintype "passive"))
      (node (ref "P5") (pin "10") (pinfunction "PAD2_10") (pintype "passive"))
      (node (ref "P5") (pin "6") (pinfunction "VSS_6") (pintype "passive"))
      (node (ref "P5") (pin "9") (pinfunction "PAD1_9") (pintype "passive"))
      (node (ref "P6") (pin "3") (pinfunction "3_3") (pintype "passive"))
      (node (ref "Q24") (pin "2") (pinfunction "E_2") (pintype "passive"))
      (node (ref "R117") (pin "2") (pinfunction "2_2") (pintype "passive"))
      (node (ref "U6") (pin "10") (pinfunction "VSS_5_10") (pintype "passive"))
      (node (ref "U6") (pin "19") (pinfunction "VSSA_19") (pintype "passive"))
      (node (ref "U6") (pin "20") (pinfunction "VREF-_20") (pintype "passive"))
      (node (ref "U6") (pin "27") (pinfunction "VSS_4_27") (pintype "passive"))
      (node (ref "U6") (pin "49") (pinfunction "VSS_1_49") (pintype "passive"))
      (node (ref "U6") (pin "74") (pinfunction "VSS_2_74") (pintype "passive"))
      (node (ref "U6") (pin "94") (pinfunction "BOOT0_94") (pintype "passive"))
      (node (ref "U6") (pin "99") (pinfunction "VSS_3_99") (pintype "passive"))
      (node (ref "U7") (pin "4") (pinfunction "GND_4") (pintype "passive"))
      (node (ref "Y1") (pin "2") (pinfunction "GND_2") (pintype "passive"))
      (node (ref "Y1") (pin "3") (pinfunction "GND_3") (pintype "passive"))
      (node (ref "Y2") (pin "2") (pinfunction "Case_2") (pintype "passive"))
      (node (ref "Y2") (pin "4") (pinfunction "Case_4") (pintype "passive"))
    )
    (net (code "82") (name "Net-(BU1-PIN2)") (class "Default")
      (node (ref "BU1") (pin "2") (pinfunction "PIN2_2") (pintype "passive"))
      (node (ref "C75") (pin "1") (pinfunction "1_1") (pintype "passive"))
      (node (ref "Q24") (pin "3") (pinfunction "C_3") (pintype "passive"))
    )
    (net (code "83") (name "Net-(IC2-RXD)") (class "Default")
      (node (ref "IC2") (pin "5") (pinfunction "RXD_5") (pintype "passive"))
      (node (ref "R24") (pin "2") (pinfunction "2_2") (pintype "passive"))
    )
    (net (code "84") (name "Net-(IC2-TXD)") (class "Default")
      (node (ref "IC2") (pin "1") (pinfunction "TXD_1") (pintype "passive"))
      (node (ref "R17") (pin "2") (pinfunction "2_2") (pintype "passive"))
    )
    (net (code "85") (name "Net-(Q24-B)") (class "Default")
      (node (ref "Q24") (pin "1") (pinfunction "B_1") (pintype "passive"))
      (node (ref "R116") (pin "1") (pinfunction "1_1") (pintype "passive"))
      (node (ref "R117") (pin "1") (pinfunction "1_1") (pintype "passive"))
    )
    (net (code "86") (name "U3V3") (class "Default")
      (node (ref "C80") (pin "1") (pinfunction "1_1") (pintype "passive"))
      (node (ref "IC2") (pin "17") (pinfunction "3V3OUT_17") (pintype "passive"))
      (node (ref "IC2") (pin "4") (pinfunction "VCCIO_4") (pintype "passive"))
    )
    (net (code "87") (name "unconnected-(BAT1-+3V-Pad1)") (class "Default")
      (node (ref "BAT1") (pin "1") (pinfunction "+3V_1") (pintype "passive+no_connect"))
    )
    (net (code "88") (name "unconnected-(BAT1-GND-Pad2)") (class "Default")
      (node (ref "BAT1") (pin "2") (pinfunction "GND_2") (pintype "passive+no_connect"))
    )
    (net (code "89") (name "unconnected-(IC2-CBUS0-Pad23)") (class "Default")
      (node (ref "IC2") (pin "23") (pinfunction "CBUS0_23") (pintype "passive+no_connect"))
    )
    (net (code "90") (name "unconnected-(IC2-CBUS1-Pad22)") (class "Default")
      (node (ref "IC2") (pin "22") (pinfunction "CBUS1_22") (pintype "passive+no_connect"))
    )
    (net (code "91") (name "unconnected-(IC2-CBUS2-Pad13)") (class "Default")
      (node (ref "IC2") (pin "13") (pinfunction "CBUS2_13") (pintype "passive+no_connect"))
    )
    (net (code "92") (name "unconnected-(IC2-CBUS3-Pad12)") (class "Default")
      (node (ref "IC2") (pin "12") (pinfunction "CBUS3_12") (pintype "passive+no_connect"))
    )
    (net (code "93") (name "unconnected-(IC2-CBUS3-Pad14)") (class "Default")
      (node (ref "IC2") (pin "14") (pinfunction "CBUS3_14") (pintype "passive+no_connect"))
    )
    (net (code "94") (name "unconnected-(IC2-CTS#-Pad11)") (class "Default")
      (node (ref "IC2") (pin "11") (pinfunction "CTS#_11") (pintype "passive+no_connect"))
    )
    (net (code "95") (name "unconnected-(IC2-DCD#-Pad10)") (class "Default")
      (node (ref "IC2") (pin "10") (pinfunction "DCD#_10") (pintype "passive+no_connect"))
    )
    (net (code "96") (name "unconnected-(IC2-DSR#-Pad9)") (class "Default")
      (node (ref "IC2") (pin "9") (pinfunction "DSR#_9") (pintype "passive+no_connect"))
    )
    (net (code "97") (name "unconnected-(IC2-DTR#-Pad2)") (class "Default")
      (node (ref "IC2") (pin "2") (pinfunction "DTR#_2") (pintype "passive+no_connect"))
    )
    (net (code "98") (name "unconnected-(IC2-NC-Pad8)") (class "Default")
      (node (ref "IC2") (pin "8") (pinfunction "NC_8") (pintype "passive+no_connect"))
    )
    (net (code "99") (name "unconnected-(IC2-NC-Pad24)") (class "Default")
      (node (ref "IC2") (pin "24") (pinfunction "NC_24") (pintype "passive+no_connect"))
    )
    (net (code "100") (name "unconnected-(IC2-OSCI-Pad27)") (class "Default")
      (node (ref "IC2") (pin "27") (pinfunction "OSCI_27") (pintype "passive+no_connect"))
    )
    (net (code "101") (name "unconnected-(IC2-OSCO-Pad28)") (class "Default")
      (node (ref "IC2") (pin "28") (pinfunction "OSCO_28") (pintype "passive+no_connect"))
    )
    (net (code "102") (name "unconnected-(IC2-RESET#-Pad19)") (class "Default")
      (node (ref "IC2") (pin "19") (pinfunction "RESET#_19") (pintype "passive+no_connect"))
    )
    (net (code "103") (name "unconnected-(IC2-RI#-Pad6)") (class "Default")
      (node (ref "IC2") (pin "6") (pinfunction "RI#_6") (pintype "passive+no_connect"))
    )
    (net (code "104") (name "unconnected-(IC2-RTS#-Pad3)") (class "Default")
      (node (ref "IC2") (pin "3") (pinfunction "RTS#_3") (pintype "passive+no_connect"))
    )
    (net (code "105") (name "unconnected-(J1-CC1_A-PadA5)") (class "Default")
      (node (ref "J1") (pin "A5") (pinfunction "CC1_A_A5") (pintype "bidirectional"))
    )
    (net (code "106") (name "unconnected-(J1-CC2_B-PadB5)") (class "Default")
      (node (ref "J1") (pin "B5") (pinfunction "CC2_B_B5") (pintype "bidirectional"))
    )
    (net (code "107") (name "unconnected-(J1-SBU1-PadA8)") (class "Default")
      (node (ref "J1") (pin "A8") (pinfunction "SBU1_A8") (pintype "bidirectional"))
    )
    (net (code "108") (name "unconnected-(J1-SBU2-PadB8)") (class "Default")
      (node (ref "J1") (pin "B8") (pinfunction "SBU2_B8") (pintype "bidirectional"))
    )
    (net (code "109") (name "unconnected-(U6-NC-Pad73)") (class "Default")
      (node (ref "U6") (pin "73") (pinfunction "NC_73") (pintype "passive"))
    )
    (net (code "110") (name "unconnected-(U6-PA11{slash}USART1_CTS{slash}USB_DM{slash}CAN_RX{slash}RIM1_CH4-Pad70)") (class "Default")
      (node (ref "U6") (pin "70") (pinfunction "PA11/USART1_CTS/USB_DM/CAN_RX/RIM1_CH4_70") (pintype "passive"))
    )
    (net (code "111") (name "unconnected-(U6-PA12{slash}USART1_RTS{slash}USB_DP{slash}CAN_TX{slash}TIM1_ETR-Pad71)") (class "Default")
      (node (ref "U6") (pin "71") (pinfunction "PA12/USART1_RTS/USB_DP/CAN_TX/TIM1_ETR_71") (pintype "passive"))
    )
    (net (code "112") (name "unconnected-(U6-PA15{slash}JTDI{slash}SPI3_NSS{slash}I2S3_WS{slash}TIM2_CH1_ETR-Pad77)") (class "Default")
      (node (ref "U6") (pin "77") (pinfunction "PA15/JTDI/SPI3_NSS/I2S3_WS/TIM2_CH1_ETR_77") (pintype "passive"))
    )
    (net (code "113") (name "unconnected-(U6-PB8{slash}TIM4_CH3{slash}SDIO_D4{slash}I2C1_SCL{slash}CAN_RX-Pad95)") (class "Default")
      (node (ref "U6") (pin "95") (pinfunction "PB8/TIM4_CH3/SDIO_D4/I2C1_SCL/CAN_RX_95") (pintype "passive"))
    )
    (net (code "114") (name "unconnected-(U6-PB9{slash}TIM4_CH4{slash}SDIO_D5{slash}I2C1_SDA{slash}CAN_TX-Pad96)") (class "Default")
      (node (ref "U6") (pin "96") (pinfunction "PB9/TIM4_CH4/SDIO_D5/I2C1_SDA/CAN_TX_96") (pintype "passive"))
    )
    (net (code "115") (name "unconnected-(U6-PC2{slash}ADC123_IN12-Pad17)") (class "Default")
      (node (ref "U6") (pin "17") (pinfunction "PC2/ADC123_IN12_17") (pintype "passive"))
    )
    (net (code "116") (name "unconnected-(U6-PC13{slash}TAMPER-RTC-Pad7)") (class "Default")
      (node (ref "U6") (pin "7") (pinfunction "PC13/TAMPER-RTC_7") (pintype "passive"))
    )
    (net (code "117") (name "unconnected-(U6-PD0{slash}OSC_IN{slash}FSMC_D2{slash}CAN_RX-Pad81)") (class "Default")
      (node (ref "U6") (pin "81") (pinfunction "PD0/OSC_IN/FSMC_D2/CAN_RX_81") (pintype "passive"))
    )
    (net (code "118") (name "unconnected-(U6-PD1{slash}OSC_OUT{slash}FSMC_D3{slash}CAN_TX-Pad82)") (class "Default")
      (node (ref "U6") (pin "82") (pinfunction "PD1/OSC_OUT/FSMC_D3/CAN_TX_82") (pintype "passive"))
    )
    (net (code "119") (name "unconnected-(U6-PD3{slash}FSMC_CLK{slash}USART2_CTS-Pad84)") (class "Default")
      (node (ref "U6") (pin "84") (pinfunction "PD3/FSMC_CLK/USART2_CTS_84") (pintype "passive"))
    )
    (net (code "120") (name "unconnected-(U6-PD4{slash}FSMC_NOE{slash}USART2_RTS-Pad85)") (class "Default")
      (node (ref "U6") (pin "85") (pinfunction "PD4/FSMC_NOE/USART2_RTS_85") (pintype "passive"))
    )
    (net (code "121") (name "unconnected-(U6-PE0{slash}TIM4_ETR{slash}FSMC_NBL0-Pad97)") (class "Default")
      (node (ref "U6") (pin "97") (pinfunction "PE0/TIM4_ETR/FSMC_NBL0_97") (pintype "passive"))
    )
    (net (code "122") (name "unconnected-(U6-PE1{slash}FSMC_NBL1-Pad98)") (class "Default")
      (node (ref "U6") (pin "98") (pinfunction "PE1/FSMC_NBL1_98") (pintype "passive"))
    )
    (net (code "123") (name "unconnected-(U6-PE2{slash}TRACECK{slash}FSMC_A23-Pad1)") (class "Default")
      (node (ref "U6") (pin "1") (pinfunction "PE2/TRACECK/FSMC_A23_1") (pintype "passive"))
    )
    (net (code "124") (name "unconnected-(U6-PE3{slash}TRACED0{slash}FSMC_A19-Pad2)") (class "Default")
      (node (ref "U6") (pin "2") (pinfunction "PE3/TRACED0/FSMC_A19_2") (pintype "passive"))
    )
    (net (code "125") (name "unconnected-(U6-PE4{slash}TRCED1{slash}FSMC_A20-Pad3)") (class "Default")
      (node (ref "U6") (pin "3") (pinfunction "PE4/TRCED1/FSMC_A20_3") (pintype "passive"))
    )
    (net (code "126") (name "unconnected-(U6-PE5{slash}TRACED2{slash}FSMC_A21-Pad4)") (class "Default")
      (node (ref "U6") (pin "4") (pinfunction "PE5/TRACED2/FSMC_A21_4") (pintype "passive"))
    )
    (net (code "127") (name "unconnected-(U6-PE6{slash}TRACED3{slash}FSMC_A22-Pad5)") (class "Default")
      (node (ref "U6") (pin "5") (pinfunction "PE6/TRACED3/FSMC_A22_5") (pintype "passive"))
    )
  )
)
